# Wilssen_core_v0_203a.net
KiCad netlist of a schematic drawn in EAGLE
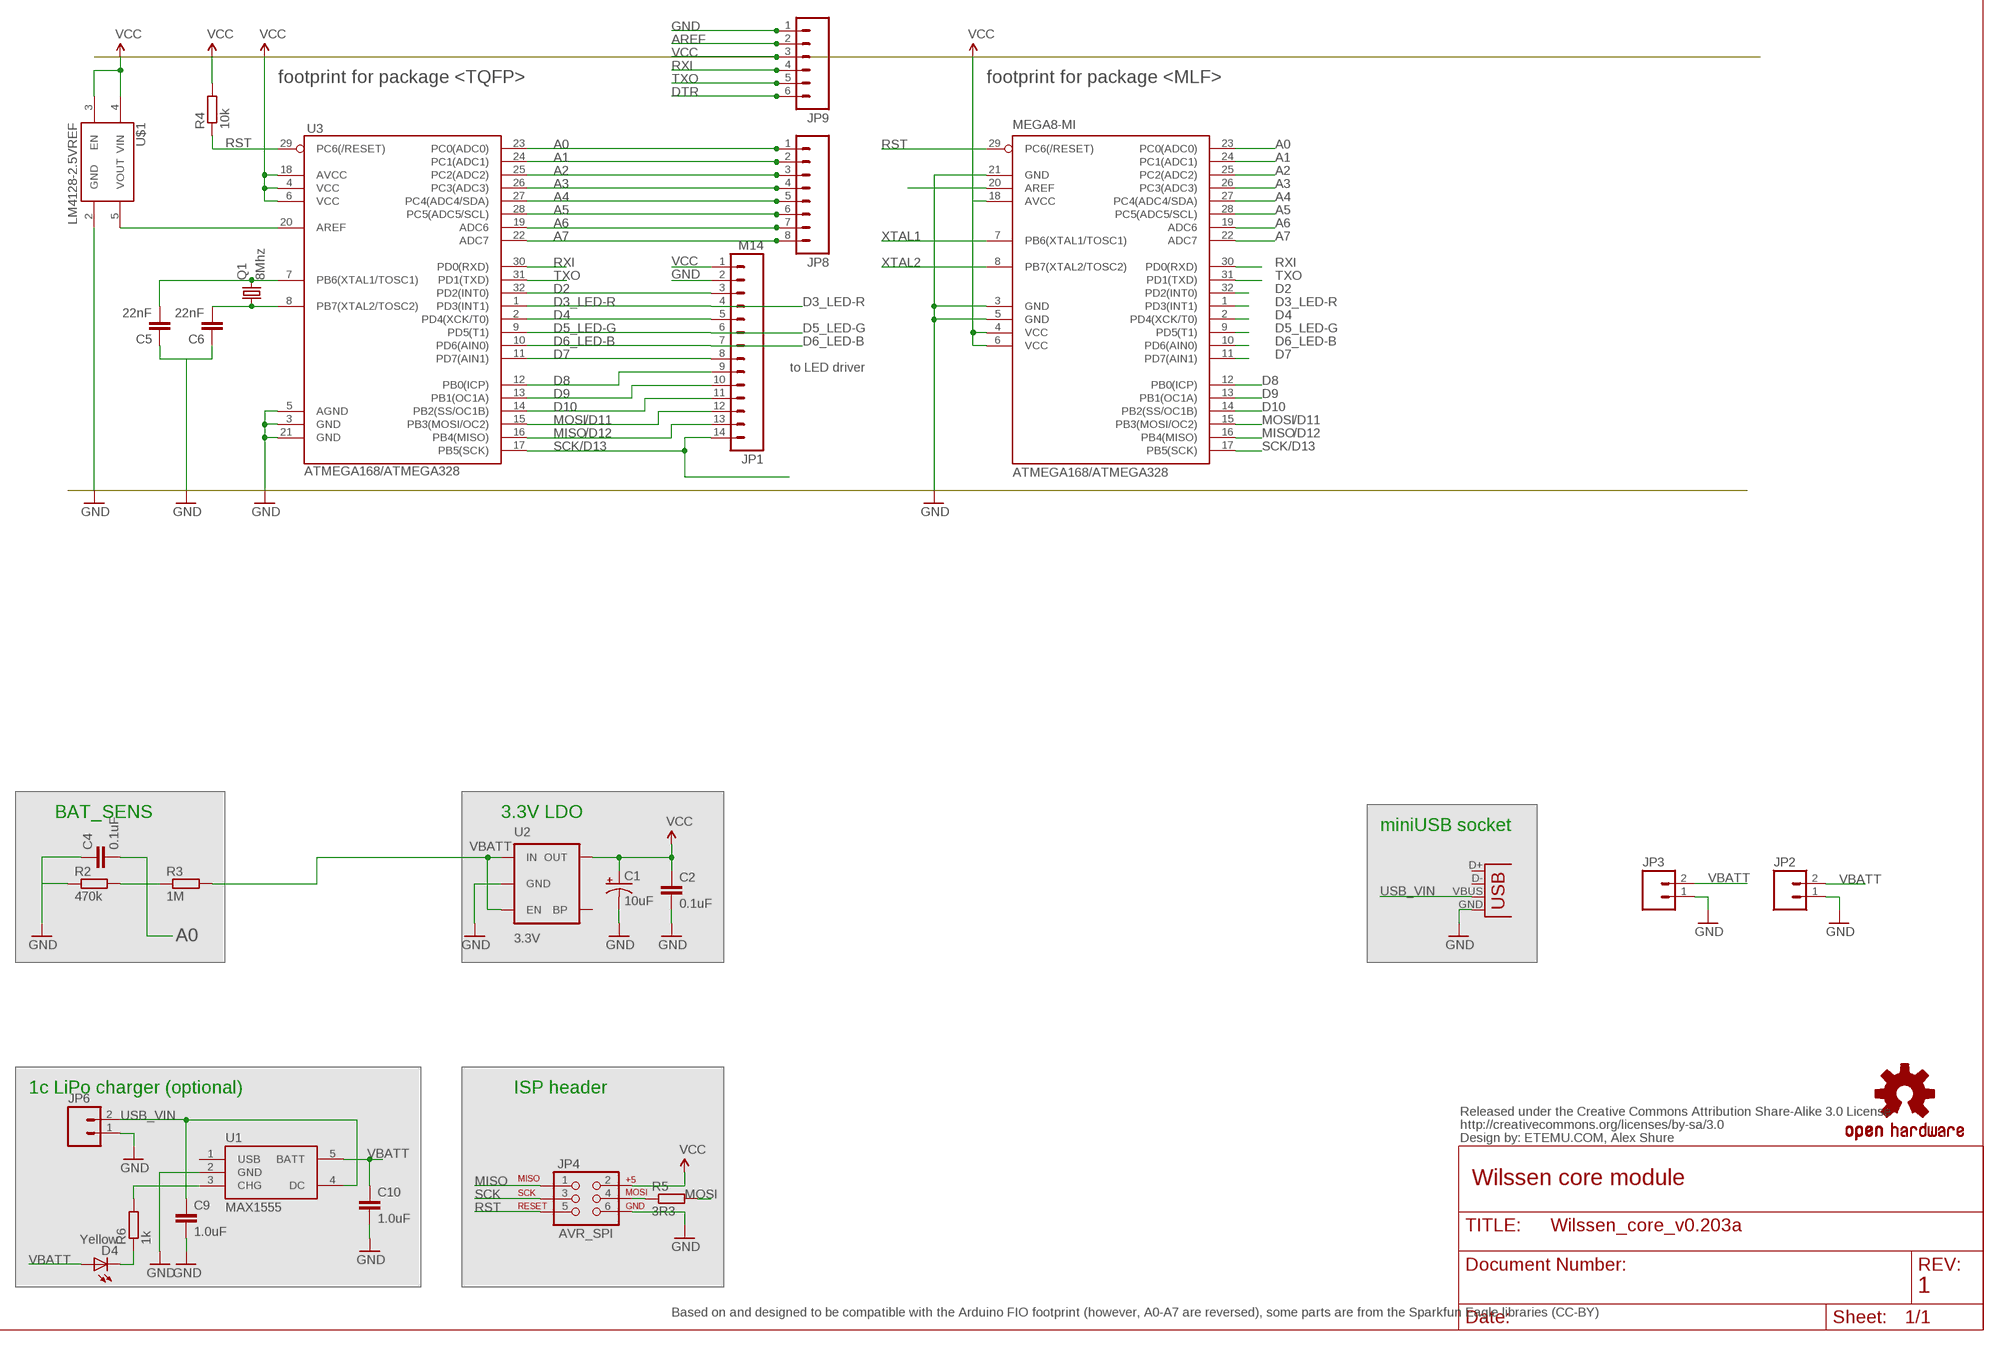
[diagram p0: schematic, sheet 1, part 1 of 2]
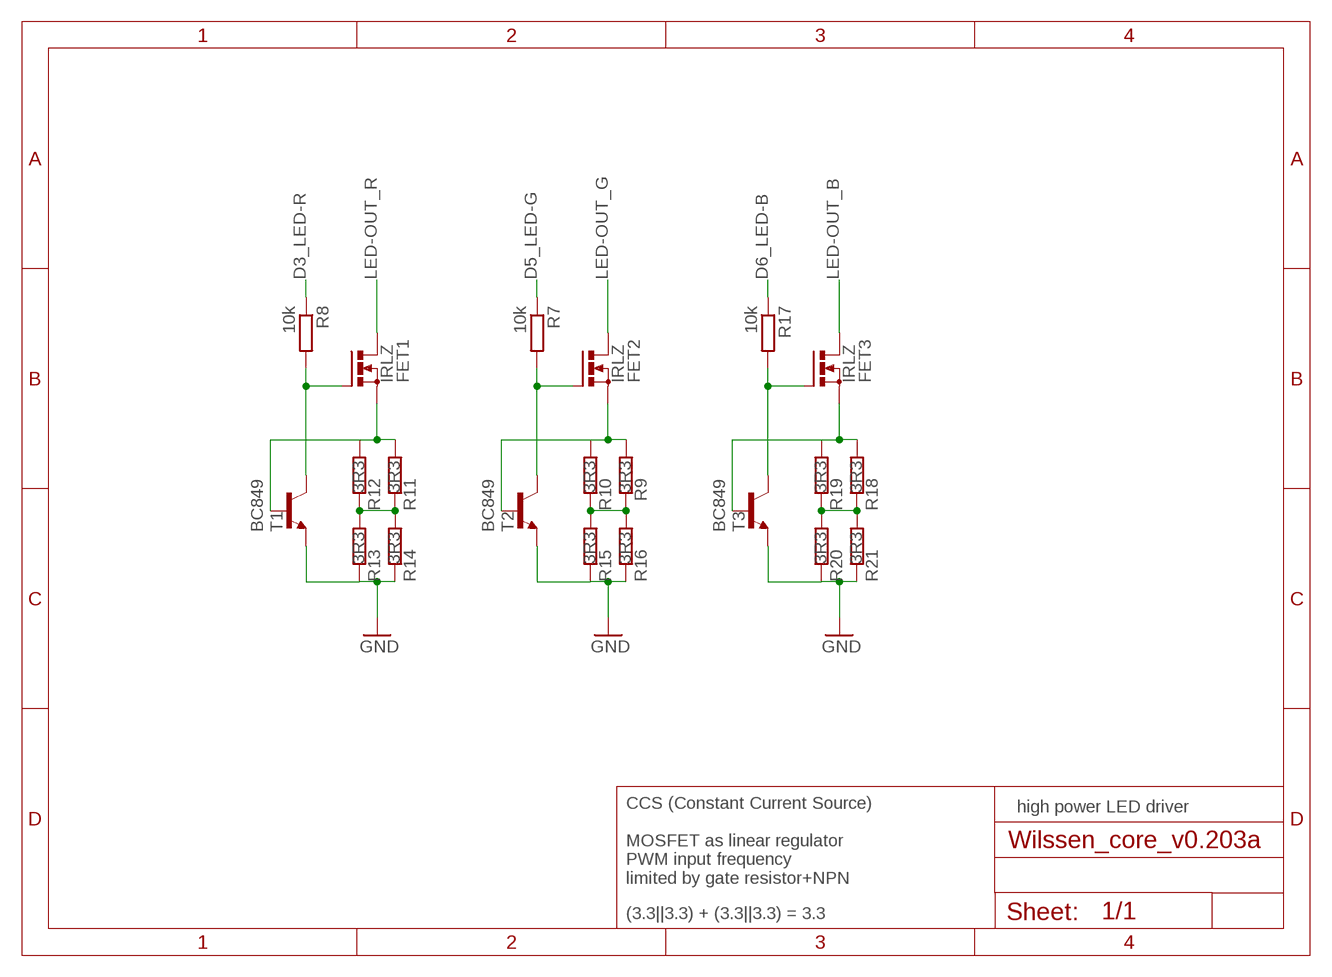
[diagram p1: schematic, sheet 1, part 2 of 2]

(export (version "E")
  (design (tool "Eeschema 10.0.6"))
  (components
    (comp (ref "ATMEGA168/ATMEGA328")
      (value "MEGA8-MI")
      (footprint "eagle-import:MLF32")
      (fields (field (name "MPN") "ATMEGA88PA-MU"))
      (libsource (lib "eagle-import") (part "MEGA8-MI"))
    )
    (comp (ref "C1")
      (value "10uF")
      (footprint "eagle-import:EIA3216")
      (libsource (lib "eagle-import") (part "CAP_POL1206"))
    )
    (comp (ref "C2")
      (value "0.1uF")
      (footprint "eagle-import:0805")
      (libsource (lib "eagle-import") (part "CAP0805"))
    )
    (comp (ref "C4")
      (value "0.1uF")
      (footprint "eagle-import:0805")
      (libsource (lib "eagle-import") (part "CAP0805"))
    )
    (comp (ref "C5")
      (value "22nF")
      (footprint "eagle-import:0805")
      (libsource (lib "eagle-import") (part "CAP0805"))
    )
    (comp (ref "C6")
      (value "22nF")
      (footprint "eagle-import:0805")
      (libsource (lib "eagle-import") (part "CAP0805"))
    )
    (comp (ref "C9")
      (value "1.0uF")
      (footprint "eagle-import:0805")
      (libsource (lib "eagle-import") (part "CAP0805"))
    )
    (comp (ref "C10")
      (value "1.0uF")
      (footprint "eagle-import:0805")
      (libsource (lib "eagle-import") (part "CAP0805"))
    )
    (comp (ref "CC_TEXT1")
      (value "CREATIVE_COMMONS")
      (footprint "eagle-import:CREATIVE_COMMONS")
      (libsource (lib "eagle-import") (part "CREATIVE_COMMONS"))
    )
    (comp (ref "D4")
      (value "Yellow")
      (footprint "eagle-import:LED-0603")
      (libsource (lib "eagle-import") (part "LED0603"))
    )
    (comp (ref "FET1")
      (value "IRLZ")
      (footprint "eagle-import:TO220BV")
      (libsource (lib "eagle-import") (part "PMOSFET_NTO220BV"))
    )
    (comp (ref "FET2")
      (value "IRLZ")
      (footprint "eagle-import:TO220BV")
      (libsource (lib "eagle-import") (part "PMOSFET_NTO220BV"))
    )
    (comp (ref "FET3")
      (value "IRLZ")
      (footprint "eagle-import:TO220BV")
      (libsource (lib "eagle-import") (part "PMOSFET_NTO220BV"))
    )
    (comp (ref "JP1")
      (value "M14")
      (footprint "eagle-import:1X14")
      (libsource (lib "eagle-import") (part "M14"))
    )
    (comp (ref "JP2")
      (value "M02PTH")
      (footprint "eagle-import:1X02")
      (libsource (lib "eagle-import") (part "M02PTH"))
    )
    (comp (ref "JP3")
      (value "M02-JST-2MM-SMT")
      (footprint "eagle-import:S2B-PH")
      (libsource (lib "eagle-import") (part "M02-JST-2MM-SMT"))
    )
    (comp (ref "JP4")
      (value "AVR_SPI")
      (footprint "eagle-import:2X3")
      (libsource (lib "eagle-import") (part "AVR_SPI_PRG_6PTH"))
    )
    (comp (ref "JP6")
      (value "M02PTH")
      (footprint "eagle-import:1X02")
      (libsource (lib "eagle-import") (part "M02PTH"))
    )
    (comp (ref "JP8")
      (value "M081X08")
      (footprint "eagle-import:1X08")
      (libsource (lib "eagle-import") (part "M081X08"))
    )
    (comp (ref "JP9")
      (value "M06SIP")
      (footprint "eagle-import:1X06")
      (libsource (lib "eagle-import") (part "M06SIP"))
    )
    (comp (ref "LOGO1")
      (value "OSHW-LOGOS")
      (footprint "eagle-import:OSHW-LOGO-S")
      (libsource (lib "eagle-import") (part "OSHW-LOGOS"))
    )
    (comp (ref "Q1")
      (value "8Mhz")
      (footprint "eagle-import:SM49")
      (libsource (lib "eagle-import") (part "CRYSTALSM49"))
    )
    (comp (ref "R2")
      (value "470k")
      (footprint "eagle-import:R0805")
      (libsource (lib "eagle-import") (part "R-EU_R0805"))
    )
    (comp (ref "R3")
      (value "1M")
      (footprint "eagle-import:R0805")
      (libsource (lib "eagle-import") (part "R-EU_R0805"))
    )
    (comp (ref "R4")
      (value "10k")
      (footprint "eagle-import:R0805")
      (libsource (lib "eagle-import") (part "R-EU_R0805"))
    )
    (comp (ref "R5")
      (value "3R3")
      (footprint "eagle-import:R1206")
      (libsource (lib "eagle-import") (part "R-EU_R1206"))
    )
    (comp (ref "R6")
      (value "1k")
      (footprint "eagle-import:R0805")
      (libsource (lib "eagle-import") (part "R-EU_R0805"))
    )
    (comp (ref "R7")
      (value "10k")
      (footprint "eagle-import:R0805")
      (libsource (lib "eagle-import") (part "resistor_R-EU_R0805"))
    )
    (comp (ref "R8")
      (value "10k")
      (footprint "eagle-import:R0805")
      (libsource (lib "eagle-import") (part "resistor_R-EU_R0805"))
    )
    (comp (ref "R9")
      (value "3R3")
      (footprint "eagle-import:R1206")
      (libsource (lib "eagle-import") (part "resistor_R-EU_R1206"))
    )
    (comp (ref "R10")
      (value "3R3")
      (footprint "eagle-import:R1206")
      (libsource (lib "eagle-import") (part "resistor_R-EU_R1206"))
    )
    (comp (ref "R11")
      (value "3R3")
      (footprint "eagle-import:R1206")
      (libsource (lib "eagle-import") (part "resistor_R-EU_R1206"))
    )
    (comp (ref "R12")
      (value "3R3")
      (footprint "eagle-import:R1206")
      (libsource (lib "eagle-import") (part "resistor_R-EU_R1206"))
    )
    (comp (ref "R13")
      (value "3R3")
      (footprint "eagle-import:R1206")
      (libsource (lib "eagle-import") (part "resistor_R-EU_R1206"))
    )
    (comp (ref "R14")
      (value "3R3")
      (footprint "eagle-import:R1206")
      (libsource (lib "eagle-import") (part "resistor_R-EU_R1206"))
    )
    (comp (ref "R15")
      (value "3R3")
      (footprint "eagle-import:R1206")
      (libsource (lib "eagle-import") (part "resistor_R-EU_R1206"))
    )
    (comp (ref "R16")
      (value "3R3")
      (footprint "eagle-import:R1206")
      (libsource (lib "eagle-import") (part "resistor_R-EU_R1206"))
    )
    (comp (ref "R17")
      (value "10k")
      (footprint "eagle-import:R0805")
      (libsource (lib "eagle-import") (part "resistor_R-EU_R0805"))
    )
    (comp (ref "R18")
      (value "3R3")
      (footprint "eagle-import:R1206")
      (libsource (lib "eagle-import") (part "resistor_R-EU_R1206"))
    )
    (comp (ref "R19")
      (value "3R3")
      (footprint "eagle-import:R1206")
      (libsource (lib "eagle-import") (part "resistor_R-EU_R1206"))
    )
    (comp (ref "R20")
      (value "3R3")
      (footprint "eagle-import:R1206")
      (libsource (lib "eagle-import") (part "resistor_R-EU_R1206"))
    )
    (comp (ref "R21")
      (value "3R3")
      (footprint "eagle-import:R1206")
      (libsource (lib "eagle-import") (part "resistor_R-EU_R1206"))
    )
    (comp (ref "T1")
      (value "BC849")
      (footprint "eagle-import:SOT23")
      (libsource (lib "eagle-import") (part "BC849"))
    )
    (comp (ref "T2")
      (value "BC849")
      (footprint "eagle-import:SOT23")
      (libsource (lib "eagle-import") (part "BC849"))
    )
    (comp (ref "T3")
      (value "BC849")
      (footprint "eagle-import:SOT23")
      (libsource (lib "eagle-import") (part "BC849"))
    )
    (comp (ref "U$1")
      (value "LM4128-2.5VREF")
      (footprint "eagle-import:SOT23-5")
      (libsource (lib "eagle-import") (part "LM4128-2.5VREF"))
    )
    (comp (ref "U1")
      (value "MAX1555")
      (footprint "eagle-import:SOT23-5")
      (libsource (lib "eagle-import") (part "MAX1555"))
    )
    (comp (ref "U2")
      (value "3.3V")
      (footprint "eagle-import:SOT23-5")
      (libsource (lib "eagle-import") (part "V_REG_LDOSMD"))
    )
    (comp (ref "U3")
      (value "ATMEGA168/ATMEGA328")
      (footprint "eagle-import:TQFP32-08")
      (libsource (lib "eagle-import") (part "ATMEGA168"))
    )
    (comp (ref "X1")
      (value "USBSMD")
      (footprint "eagle-import:USB-MINIB")
      (libsource (lib "eagle-import") (part "USBSMD"))
    )
  )
  (nets
    (net (code "1") (name "/A0") (class "Default")
      (node (ref "ATMEGA168/ATMEGA328") (pin "23") (pinfunction "PC0(ADC0)_23") (pintype "bidirectional"))
      (node (ref "C4") (pin "2") (pinfunction "2_2") (pintype "passive"))
      (node (ref "JP8") (pin "1") (pinfunction "1_1") (pintype "passive"))
      (node (ref "R2") (pin "2") (pinfunction "2_2") (pintype "passive"))
      (node (ref "R3") (pin "1") (pinfunction "1_1") (pintype "passive"))
      (node (ref "U3") (pin "23") (pinfunction "PC0(ADC0)_23") (pintype "bidirectional"))
    )
    (net (code "2") (name "/A1") (class "Default")
      (node (ref "ATMEGA168/ATMEGA328") (pin "24") (pinfunction "PC1(ADC1)_24") (pintype "bidirectional"))
      (node (ref "JP8") (pin "2") (pinfunction "2_2") (pintype "passive"))
      (node (ref "U3") (pin "24") (pinfunction "PC1(ADC1)_24") (pintype "bidirectional"))
    )
    (net (code "3") (name "/A2") (class "Default")
      (node (ref "ATMEGA168/ATMEGA328") (pin "25") (pinfunction "PC2(ADC2)_25") (pintype "bidirectional"))
      (node (ref "JP8") (pin "3") (pinfunction "3_3") (pintype "passive"))
      (node (ref "U3") (pin "25") (pinfunction "PC2(ADC2)_25") (pintype "bidirectional"))
    )
    (net (code "4") (name "/A3") (class "Default")
      (node (ref "ATMEGA168/ATMEGA328") (pin "26") (pinfunction "PC3(ADC3)_26") (pintype "bidirectional"))
      (node (ref "JP8") (pin "4") (pinfunction "4_4") (pintype "passive"))
      (node (ref "U3") (pin "26") (pinfunction "PC3(ADC3)_26") (pintype "bidirectional"))
    )
    (net (code "5") (name "/A4") (class "Default")
      (node (ref "ATMEGA168/ATMEGA328") (pin "27") (pinfunction "PC4(ADC4/SDA)_27") (pintype "bidirectional"))
      (node (ref "JP8") (pin "5") (pinfunction "5_5") (pintype "passive"))
      (node (ref "U3") (pin "27") (pinfunction "PC4(ADC4/SDA)_27") (pintype "bidirectional"))
    )
    (net (code "6") (name "/A5") (class "Default")
      (node (ref "ATMEGA168/ATMEGA328") (pin "28") (pinfunction "PC5(ADC5/SCL)_28") (pintype "bidirectional"))
      (node (ref "JP8") (pin "6") (pinfunction "6_6") (pintype "passive"))
      (node (ref "U3") (pin "28") (pinfunction "PC5(ADC5/SCL)_28") (pintype "bidirectional"))
    )
    (net (code "7") (name "/A6") (class "Default")
      (node (ref "ATMEGA168/ATMEGA328") (pin "19") (pinfunction "ADC6_19") (pintype "bidirectional"))
      (node (ref "JP8") (pin "7") (pinfunction "7_7") (pintype "passive"))
      (node (ref "U3") (pin "19") (pinfunction "ADC6_19") (pintype "bidirectional"))
    )
    (net (code "8") (name "/A7") (class "Default")
      (node (ref "ATMEGA168/ATMEGA328") (pin "22") (pinfunction "ADC7_22") (pintype "bidirectional"))
      (node (ref "JP8") (pin "8") (pinfunction "8_8") (pintype "passive"))
      (node (ref "U3") (pin "22") (pinfunction "ADC7_22") (pintype "bidirectional"))
    )
    (net (code "9") (name "/AREF") (class "Default")
      (node (ref "ATMEGA168/ATMEGA328") (pin "20") (pinfunction "AREF_20") (pintype "passive"))
      (node (ref "JP9") (pin "2") (pinfunction "2_2") (pintype "passive"))
      (node (ref "U$1") (pin "5") (pinfunction "VOUT_5") (pintype "bidirectional"))
      (node (ref "U3") (pin "20") (pinfunction "AREF_20") (pintype "bidirectional"))
    )
    (net (code "10") (name "/D2") (class "Default")
      (node (ref "ATMEGA168/ATMEGA328") (pin "32") (pinfunction "PD2(INT0)_32") (pintype "bidirectional"))
      (node (ref "JP1") (pin "3") (pinfunction "3_3") (pintype "passive"))
      (node (ref "U3") (pin "32") (pinfunction "PD2(INT0)_32") (pintype "bidirectional"))
    )
    (net (code "11") (name "/D3_LED-R") (class "Default")
      (node (ref "ATMEGA168/ATMEGA328") (pin "1") (pinfunction "PD3(INT1)_1") (pintype "bidirectional"))
      (node (ref "JP1") (pin "4") (pinfunction "4_4") (pintype "passive"))
      (node (ref "R8") (pin "1") (pinfunction "1_1") (pintype "passive"))
      (node (ref "U3") (pin "1") (pinfunction "PD3(INT1)_1") (pintype "bidirectional"))
    )
    (net (code "12") (name "/D4") (class "Default")
      (node (ref "ATMEGA168/ATMEGA328") (pin "2") (pinfunction "PD4(XCK/T0)_2") (pintype "bidirectional"))
      (node (ref "JP1") (pin "5") (pinfunction "5_5") (pintype "passive"))
      (node (ref "U3") (pin "2") (pinfunction "PD4(XCK/T0)_2") (pintype "bidirectional"))
    )
    (net (code "13") (name "/D5_LED-G") (class "Default")
      (node (ref "ATMEGA168/ATMEGA328") (pin "9") (pinfunction "PD5(T1)_9") (pintype "bidirectional"))
      (node (ref "JP1") (pin "6") (pinfunction "6_6") (pintype "passive"))
      (node (ref "R7") (pin "1") (pinfunction "1_1") (pintype "passive"))
      (node (ref "U3") (pin "9") (pinfunction "PD5(T1)_9") (pintype "bidirectional"))
    )
    (net (code "14") (name "/D6_LED-B") (class "Default")
      (node (ref "ATMEGA168/ATMEGA328") (pin "10") (pinfunction "PD6(AIN0)_10") (pintype "bidirectional"))
      (node (ref "JP1") (pin "7") (pinfunction "7_7") (pintype "passive"))
      (node (ref "R17") (pin "1") (pinfunction "1_1") (pintype "passive"))
      (node (ref "U3") (pin "10") (pinfunction "PD6(AIN0)_10") (pintype "bidirectional"))
    )
    (net (code "15") (name "/D7") (class "Default")
      (node (ref "ATMEGA168/ATMEGA328") (pin "11") (pinfunction "PD7(AIN1)_11") (pintype "bidirectional"))
      (node (ref "JP1") (pin "8") (pinfunction "8_8") (pintype "passive"))
      (node (ref "U3") (pin "11") (pinfunction "PD7(AIN1)_11") (pintype "bidirectional"))
    )
    (net (code "16") (name "/D8") (class "Default")
      (node (ref "ATMEGA168/ATMEGA328") (pin "12") (pinfunction "PB0(ICP)_12") (pintype "bidirectional"))
      (node (ref "JP1") (pin "9") (pinfunction "9_9") (pintype "passive"))
      (node (ref "U3") (pin "12") (pinfunction "PB0(ICP)_12") (pintype "bidirectional"))
    )
    (net (code "17") (name "/D9") (class "Default")
      (node (ref "ATMEGA168/ATMEGA328") (pin "13") (pinfunction "PB1(OC1A)_13") (pintype "bidirectional"))
      (node (ref "JP1") (pin "10") (pinfunction "10_10") (pintype "passive"))
      (node (ref "U3") (pin "13") (pinfunction "PB1(OC1A)_13") (pintype "bidirectional"))
    )
    (net (code "18") (name "/D10") (class "Default")
      (node (ref "ATMEGA168/ATMEGA328") (pin "14") (pinfunction "PB2(SS/OC1B)_14") (pintype "bidirectional"))
      (node (ref "JP1") (pin "11") (pinfunction "11_11") (pintype "passive"))
      (node (ref "U3") (pin "14") (pinfunction "PB2(SS/OC1B)_14") (pintype "bidirectional"))
    )
    (net (code "19") (name "/DTR") (class "Default")
      (node (ref "JP9") (pin "6") (pinfunction "6_6") (pintype "passive"))
    )
    (net (code "20") (name "/LED-OUT_B") (class "Default")
      (node (ref "FET3") (pin "D") (pinfunction "D_D") (pintype "passive"))
    )
    (net (code "21") (name "/LED-OUT_G") (class "Default")
      (node (ref "FET2") (pin "D") (pinfunction "D_D") (pintype "passive"))
    )
    (net (code "22") (name "/LED-OUT_R") (class "Default")
      (node (ref "FET1") (pin "D") (pinfunction "D_D") (pintype "passive"))
    )
    (net (code "23") (name "/MISO") (class "Default")
      (node (ref "ATMEGA168/ATMEGA328") (pin "16") (pinfunction "PB4(MISO)_16") (pintype "bidirectional"))
      (node (ref "JP1") (pin "13") (pinfunction "13_13") (pintype "passive"))
      (node (ref "JP4") (pin "1") (pinfunction "1_1") (pintype "passive"))
      (node (ref "U3") (pin "16") (pinfunction "PB4(MISO)_16") (pintype "bidirectional"))
    )
    (net (code "24") (name "/MOSI") (class "Default")
      (node (ref "ATMEGA168/ATMEGA328") (pin "15") (pinfunction "PB3(MOSI/OC2)_15") (pintype "bidirectional"))
      (node (ref "JP1") (pin "12") (pinfunction "12_12") (pintype "passive"))
      (node (ref "R5") (pin "2") (pinfunction "2_2") (pintype "passive"))
      (node (ref "U3") (pin "15") (pinfunction "PB3(MOSI/OC2)_15") (pintype "bidirectional"))
    )
    (net (code "25") (name "/RST") (class "Default")
      (node (ref "ATMEGA168/ATMEGA328") (pin "29") (pinfunction "PC6(/RESET)_29") (pintype "bidirectional"))
      (node (ref "JP4") (pin "5") (pinfunction "5_5") (pintype "passive"))
      (node (ref "R4") (pin "1") (pinfunction "1_1") (pintype "passive"))
      (node (ref "U3") (pin "29") (pinfunction "PC6(/RESET)_29") (pintype "bidirectional"))
    )
    (net (code "26") (name "/RXI") (class "Default")
      (node (ref "ATMEGA168/ATMEGA328") (pin "30") (pinfunction "PD0(RXD)_30") (pintype "bidirectional"))
      (node (ref "JP9") (pin "4") (pinfunction "4_4") (pintype "passive"))
      (node (ref "U3") (pin "30") (pinfunction "PD0(RXD)_30") (pintype "bidirectional"))
    )
    (net (code "27") (name "/SCK") (class "Default")
      (node (ref "ATMEGA168/ATMEGA328") (pin "17") (pinfunction "PB5(SCK)_17") (pintype "bidirectional"))
      (node (ref "JP1") (pin "14") (pinfunction "14_14") (pintype "passive"))
      (node (ref "JP4") (pin "3") (pinfunction "3_3") (pintype "passive"))
      (node (ref "U3") (pin "17") (pinfunction "PB5(SCK)_17") (pintype "bidirectional"))
    )
    (net (code "28") (name "/TXO") (class "Default")
      (node (ref "ATMEGA168/ATMEGA328") (pin "31") (pinfunction "PD1(TXD)_31") (pintype "bidirectional"))
      (node (ref "JP9") (pin "5") (pinfunction "5_5") (pintype "passive"))
      (node (ref "U3") (pin "31") (pinfunction "PD1(TXD)_31") (pintype "bidirectional"))
    )
    (net (code "29") (name "/USB_VIN") (class "Default")
      (node (ref "C9") (pin "1") (pinfunction "1_1") (pintype "passive"))
      (node (ref "JP6") (pin "2") (pinfunction "2_2") (pintype "passive"))
      (node (ref "U1") (pin "4") (pinfunction "DC_4") (pintype "bidirectional"))
      (node (ref "X1") (pin "VBUS") (pinfunction "VBUS_VBUS") (pintype "bidirectional"))
    )
    (net (code "30") (name "/VBATT") (class "Default")
      (node (ref "C10") (pin "1") (pinfunction "1_1") (pintype "passive"))
      (node (ref "D4") (pin "A") (pinfunction "A_A") (pintype "passive"))
      (node (ref "JP2") (pin "2") (pinfunction "2_2") (pintype "passive"))
      (node (ref "JP3") (pin "2") (pinfunction "2_2") (pintype "passive"))
      (node (ref "R3") (pin "2") (pinfunction "2_2") (pintype "passive"))
      (node (ref "U1") (pin "5") (pinfunction "BATT_5") (pintype "bidirectional"))
      (node (ref "U2") (pin "1") (pinfunction "IN_1") (pintype "input"))
      (node (ref "U2") (pin "3") (pinfunction "EN_3") (pintype "input"))
    )
    (net (code "31") (name "/XTAL1") (class "Default")
      (node (ref "ATMEGA168/ATMEGA328") (pin "7") (pinfunction "PB6(XTAL1/TOSC1)_7") (pintype "bidirectional"))
      (node (ref "C5") (pin "2") (pinfunction "2_2") (pintype "passive"))
      (node (ref "Q1") (pin "2") (pinfunction "2_2") (pintype "passive"))
      (node (ref "U3") (pin "7") (pinfunction "PB6(XTAL1/TOSC1)_7") (pintype "bidirectional"))
    )
    (net (code "32") (name "/XTAL2") (class "Default")
      (node (ref "ATMEGA168/ATMEGA328") (pin "8") (pinfunction "PB7(XTAL2/TOSC2)_8") (pintype "bidirectional"))
      (node (ref "C6") (pin "2") (pinfunction "2_2") (pintype "passive"))
      (node (ref "Q1") (pin "1") (pinfunction "1_1") (pintype "passive"))
      (node (ref "U3") (pin "8") (pinfunction "PB7(XTAL2/TOSC2)_8") (pintype "bidirectional"))
    )
    (net (code "33") (name "GND") (class "Default")
      (node (ref "ATMEGA168/ATMEGA328") (pin "21") (pinfunction "GND_21") (pintype "power_in"))
      (node (ref "ATMEGA168/ATMEGA328") (pin "3") (pinfunction "GND_3") (pintype "power_in"))
      (node (ref "ATMEGA168/ATMEGA328") (pin "5") (pinfunction "GND_5") (pintype "power_in"))
      (node (ref "C1") (pin "C") (pinfunction "-_C") (pintype "passive"))
      (node (ref "C10") (pin "2") (pinfunction "2_2") (pintype "passive"))
      (node (ref "C2") (pin "2") (pinfunction "2_2") (pintype "passive"))
      (node (ref "C4") (pin "1") (pinfunction "1_1") (pintype "passive"))
      (node (ref "C5") (pin "1") (pinfunction "1_1") (pintype "passive"))
      (node (ref "C6") (pin "1") (pinfunction "1_1") (pintype "passive"))
      (node (ref "C9") (pin "2") (pinfunction "2_2") (pintype "passive"))
      (node (ref "JP1") (pin "2") (pinfunction "2_2") (pintype "passive"))
      (node (ref "JP2") (pin "1") (pinfunction "1_1") (pintype "passive"))
      (node (ref "JP3") (pin "1") (pinfunction "1_1") (pintype "passive"))
      (node (ref "JP4") (pin "6") (pinfunction "6_6") (pintype "passive"))
      (node (ref "JP6") (pin "1") (pinfunction "1_1") (pintype "passive"))
      (node (ref "JP9") (pin "1") (pinfunction "1_1") (pintype "passive"))
      (node (ref "R13") (pin "2") (pinfunction "2_2") (pintype "passive"))
      (node (ref "R14") (pin "2") (pinfunction "2_2") (pintype "passive"))
      (node (ref "R15") (pin "2") (pinfunction "2_2") (pintype "passive"))
      (node (ref "R16") (pin "2") (pinfunction "2_2") (pintype "passive"))
      (node (ref "R2") (pin "1") (pinfunction "1_1") (pintype "passive"))
      (node (ref "R20") (pin "2") (pinfunction "2_2") (pintype "passive"))
      (node (ref "R21") (pin "2") (pinfunction "2_2") (pintype "passive"))
      (node (ref "T1") (pin "2") (pinfunction "E_2") (pintype "passive"))
      (node (ref "T2") (pin "2") (pinfunction "E_2") (pintype "passive"))
      (node (ref "T3") (pin "2") (pinfunction "E_2") (pintype "passive"))
      (node (ref "U$1") (pin "2") (pinfunction "GND_2") (pintype "bidirectional"))
      (node (ref "U1") (pin "2") (pinfunction "GND_2") (pintype "bidirectional"))
      (node (ref "U2") (pin "2") (pinfunction "GND_2") (pintype "input"))
      (node (ref "U3") (pin "21") (pinfunction "GND_21") (pintype "bidirectional"))
      (node (ref "U3") (pin "3") (pinfunction "GND_3") (pintype "bidirectional"))
      (node (ref "U3") (pin "5") (pinfunction "AGND_5") (pintype "bidirectional"))
      (node (ref "X1") (pin "GND") (pinfunction "GND_GND") (pintype "bidirectional"))
    )
    (net (code "34") (name "Net-(D4-PadC)") (class "Default")
      (node (ref "D4") (pin "C") (pinfunction "C_C") (pintype "passive"))
      (node (ref "R6") (pin "1") (pinfunction "1_1") (pintype "passive"))
    )
    (net (code "35") (name "Net-(JP4-Pad4)") (class "Default")
      (node (ref "JP4") (pin "4") (pinfunction "4_4") (pintype "passive"))
      (node (ref "R5") (pin "1") (pinfunction "1_1") (pintype "passive"))
    )
    (net (code "36") (name "Net-(R10-Pad2)") (class "Default")
      (node (ref "R10") (pin "2") (pinfunction "2_2") (pintype "passive"))
      (node (ref "R15") (pin "1") (pinfunction "1_1") (pintype "passive"))
      (node (ref "R16") (pin "1") (pinfunction "1_1") (pintype "passive"))
      (node (ref "R9") (pin "2") (pinfunction "2_2") (pintype "passive"))
    )
    (net (code "37") (name "Net-(R11-Pad2)") (class "Default")
      (node (ref "R11") (pin "2") (pinfunction "2_2") (pintype "passive"))
      (node (ref "R12") (pin "2") (pinfunction "2_2") (pintype "passive"))
      (node (ref "R13") (pin "1") (pinfunction "1_1") (pintype "passive"))
      (node (ref "R14") (pin "1") (pinfunction "1_1") (pintype "passive"))
    )
    (net (code "38") (name "Net-(R18-Pad2)") (class "Default")
      (node (ref "R18") (pin "2") (pinfunction "2_2") (pintype "passive"))
      (node (ref "R19") (pin "2") (pinfunction "2_2") (pintype "passive"))
      (node (ref "R20") (pin "1") (pinfunction "1_1") (pintype "passive"))
      (node (ref "R21") (pin "1") (pinfunction "1_1") (pintype "passive"))
    )
    (net (code "39") (name "Net-(T1-B)") (class "Default")
      (node (ref "FET1") (pin "S") (pinfunction "S_S") (pintype "passive"))
      (node (ref "R11") (pin "1") (pinfunction "1_1") (pintype "passive"))
      (node (ref "R12") (pin "1") (pinfunction "1_1") (pintype "passive"))
      (node (ref "T1") (pin "1") (pinfunction "B_1") (pintype "passive"))
    )
    (net (code "40") (name "Net-(T1-C)") (class "Default")
      (node (ref "FET1") (pin "G") (pinfunction "G_G") (pintype "passive"))
      (node (ref "R8") (pin "2") (pinfunction "2_2") (pintype "passive"))
      (node (ref "T1") (pin "3") (pinfunction "C_3") (pintype "passive"))
    )
    (net (code "41") (name "Net-(T2-B)") (class "Default")
      (node (ref "FET2") (pin "S") (pinfunction "S_S") (pintype "passive"))
      (node (ref "R10") (pin "1") (pinfunction "1_1") (pintype "passive"))
      (node (ref "R9") (pin "1") (pinfunction "1_1") (pintype "passive"))
      (node (ref "T2") (pin "1") (pinfunction "B_1") (pintype "passive"))
    )
    (net (code "42") (name "Net-(T2-C)") (class "Default")
      (node (ref "FET2") (pin "G") (pinfunction "G_G") (pintype "passive"))
      (node (ref "R7") (pin "2") (pinfunction "2_2") (pintype "passive"))
      (node (ref "T2") (pin "3") (pinfunction "C_3") (pintype "passive"))
    )
    (net (code "43") (name "Net-(T3-B)") (class "Default")
      (node (ref "FET3") (pin "S") (pinfunction "S_S") (pintype "passive"))
      (node (ref "R18") (pin "1") (pinfunction "1_1") (pintype "passive"))
      (node (ref "R19") (pin "1") (pinfunction "1_1") (pintype "passive"))
      (node (ref "T3") (pin "1") (pinfunction "B_1") (pintype "passive"))
    )
    (net (code "44") (name "Net-(T3-C)") (class "Default")
      (node (ref "FET3") (pin "G") (pinfunction "G_G") (pintype "passive"))
      (node (ref "R17") (pin "2") (pinfunction "2_2") (pintype "passive"))
      (node (ref "T3") (pin "3") (pinfunction "C_3") (pintype "passive"))
    )
    (net (code "45") (name "Net-(U1-CHG)") (class "Default")
      (node (ref "R6") (pin "2") (pinfunction "2_2") (pintype "passive"))
      (node (ref "U1") (pin "3") (pinfunction "CHG_3") (pintype "bidirectional"))
    )
    (net (code "46") (name "VCC") (class "Default")
      (node (ref "ATMEGA168/ATMEGA328") (pin "18") (pinfunction "AVCC_18") (pintype "power_in"))
      (node (ref "ATMEGA168/ATMEGA328") (pin "4") (pinfunction "VCC_4") (pintype "power_in"))
      (node (ref "ATMEGA168/ATMEGA328") (pin "6") (pinfunction "VCC_6") (pintype "power_in"))
      (node (ref "C1") (pin "A") (pinfunction "+_A") (pintype "passive"))
      (node (ref "C2") (pin "1") (pinfunction "1_1") (pintype "passive"))
      (node (ref "JP1") (pin "1") (pinfunction "1_1") (pintype "passive"))
      (node (ref "JP4") (pin "2") (pinfunction "2_2") (pintype "passive"))
      (node (ref "JP9") (pin "3") (pinfunction "3_3") (pintype "passive"))
      (node (ref "R4") (pin "2") (pinfunction "2_2") (pintype "passive"))
      (node (ref "U$1") (pin "3") (pinfunction "EN_3") (pintype "bidirectional"))
      (node (ref "U$1") (pin "4") (pinfunction "VIN_4") (pintype "bidirectional"))
      (node (ref "U2") (pin "5") (pinfunction "OUT_5") (pintype "passive"))
      (node (ref "U3") (pin "18") (pinfunction "AVCC_18") (pintype "bidirectional"))
      (node (ref "U3") (pin "4") (pinfunction "VCC_4") (pintype "bidirectional"))
      (node (ref "U3") (pin "6") (pinfunction "VCC_6") (pintype "bidirectional"))
    )
    (net (code "47") (name "unconnected-(U1-USB-Pad1)") (class "Default")
      (node (ref "U1") (pin "1") (pinfunction "USB_1") (pintype "bidirectional"))
    )
    (net (code "48") (name "unconnected-(U2-BP-Pad4)") (class "Default")
      (node (ref "U2") (pin "4") (pinfunction "BP_4") (pintype "input"))
    )
    (net (code "49") (name "unconnected-(X1-PadD+)") (class "Default")
      (node (ref "X1") (pin "D+") (pinfunction "D+_D+") (pintype "bidirectional"))
    )
    (net (code "50") (name "unconnected-(X1-PadD-)") (class "Default")
      (node (ref "X1") (pin "D-") (pinfunction "D-_D-") (pintype "bidirectional"))
    )
  )
)
